# RFID_Reader.net
KiCad netlist of a schematic drawn in Altium Designer
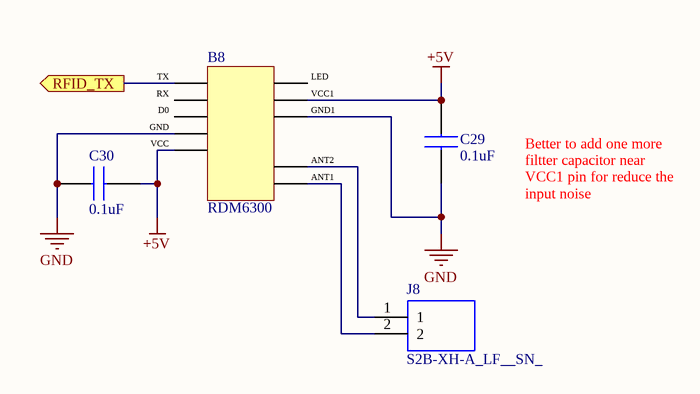
[diagram p0: RFID_Reader.SchDoc]

(export (version "E")
  (design (tool "Eeschema 10.0.6"))
  (components
    (comp (ref "B8")
      (value "RDM6300")
      (footprint "RDM6300")
      (description "RFID READER R/W 125KHZ MODULE")
      (libsource (lib "CV-R-BAP_V2.1.5") (part "RDM6300"))
    )
    (comp (ref "C29")
      (value "0.1uF")
      (footprint "CAPC1005X55N")
      (description "CAP CER 0.1UF 6.3V X7R 0402")
      (fields
        (field (name "MANUFACTURER_PART_NUMBER") "0402B104K6R3CT")
        (field (name "MOUSER PART NUMBER") "80-C0402C104M4RECTU")
      )
      (libsource (lib "0.1uF_0402") (part "C0402C104M4RECTU"))
    )
    (comp (ref "C30")
      (value "0.1uF")
      (footprint "CAPC1005X55N")
      (description "Multilayer Ceramic Capacitors MLCC - SMD/SMT 16V 0.1uF X7R 0402 20%")
      (fields
        (field (name "MANUFACTURER_PART_NUMBER") "C0402C104M4RECTU")
        (field (name "MOUSER PART NUMBER") "80-C0402C104M4RECTU")
      )
      (libsource (lib "0.1uF_0402") (part "C0402C104M4RECTU"))
    )
    (comp (ref "J8")
      (value "S2B-XH-A_LF__SN_")
      (footprint "SHDRRA2W80P0X250_1X2_740X1150X610P")
      (fields (field (name "MANUFACTURER_PART_NUMBER") "S2B-XH-A(LF)(SN)"))
      (libsource (lib "S2B-XH-A_LF__SN_") (part "S2B-XH-A_LF__SN_"))
    )
  )
  (nets
    (net (code "1") (name "+5V") (class "Default")
      (node (ref "B8") (pin "VCC") (pinfunction "VCC_VCC") (pintype "passive"))
      (node (ref "B8") (pin "VCC1") (pinfunction "VCC1_VCC1") (pintype "passive"))
      (node (ref "C29") (pin "1") (pinfunction "1_1") (pintype "passive"))
      (node (ref "C30") (pin "2") (pinfunction "2_2") (pintype "passive"))
    )
    (net (code "2") (name "/RFID_TX") (class "Default")
      (node (ref "B8") (pin "TX") (pinfunction "TX_TX") (pintype "passive"))
    )
    (net (code "3") (name "GND") (class "Default")
      (node (ref "B8") (pin "GND") (pinfunction "GND_GND") (pintype "passive"))
      (node (ref "B8") (pin "GND1") (pinfunction "GND1_GND1") (pintype "passive"))
      (node (ref "C29") (pin "2") (pinfunction "2_2") (pintype "passive"))
      (node (ref "C30") (pin "1") (pinfunction "1_1") (pintype "passive"))
    )
    (net (code "4") (name "Net-(B8-PadANT1)") (class "Default")
      (node (ref "B8") (pin "ANT1") (pinfunction "ANT1_ANT1") (pintype "passive"))
      (node (ref "J8") (pin "2") (pinfunction "2_2") (pintype "passive"))
    )
    (net (code "5") (name "Net-(B8-PadANT2)") (class "Default")
      (node (ref "B8") (pin "ANT2") (pinfunction "ANT2_ANT2") (pintype "passive"))
      (node (ref "J8") (pin "1") (pinfunction "1_1") (pintype "passive"))
    )
    (net (code "6") (name "unconnected-(B8-PadD0)") (class "Default")
      (node (ref "B8") (pin "D0") (pinfunction "D0_D0") (pintype "passive"))
    )
    (net (code "7") (name "unconnected-(B8-PadLED)") (class "Default")
      (node (ref "B8") (pin "LED") (pinfunction "LED_LED") (pintype "passive"))
    )
    (net (code "8") (name "unconnected-(B8-PadRX)") (class "Default")
      (node (ref "B8") (pin "RX") (pinfunction "RX_RX") (pintype "passive"))
    )
  )
)
